# ProPrj_32__2025-06-29.net
KiCad netlist of a schematic drawn in EasyEDA Pro
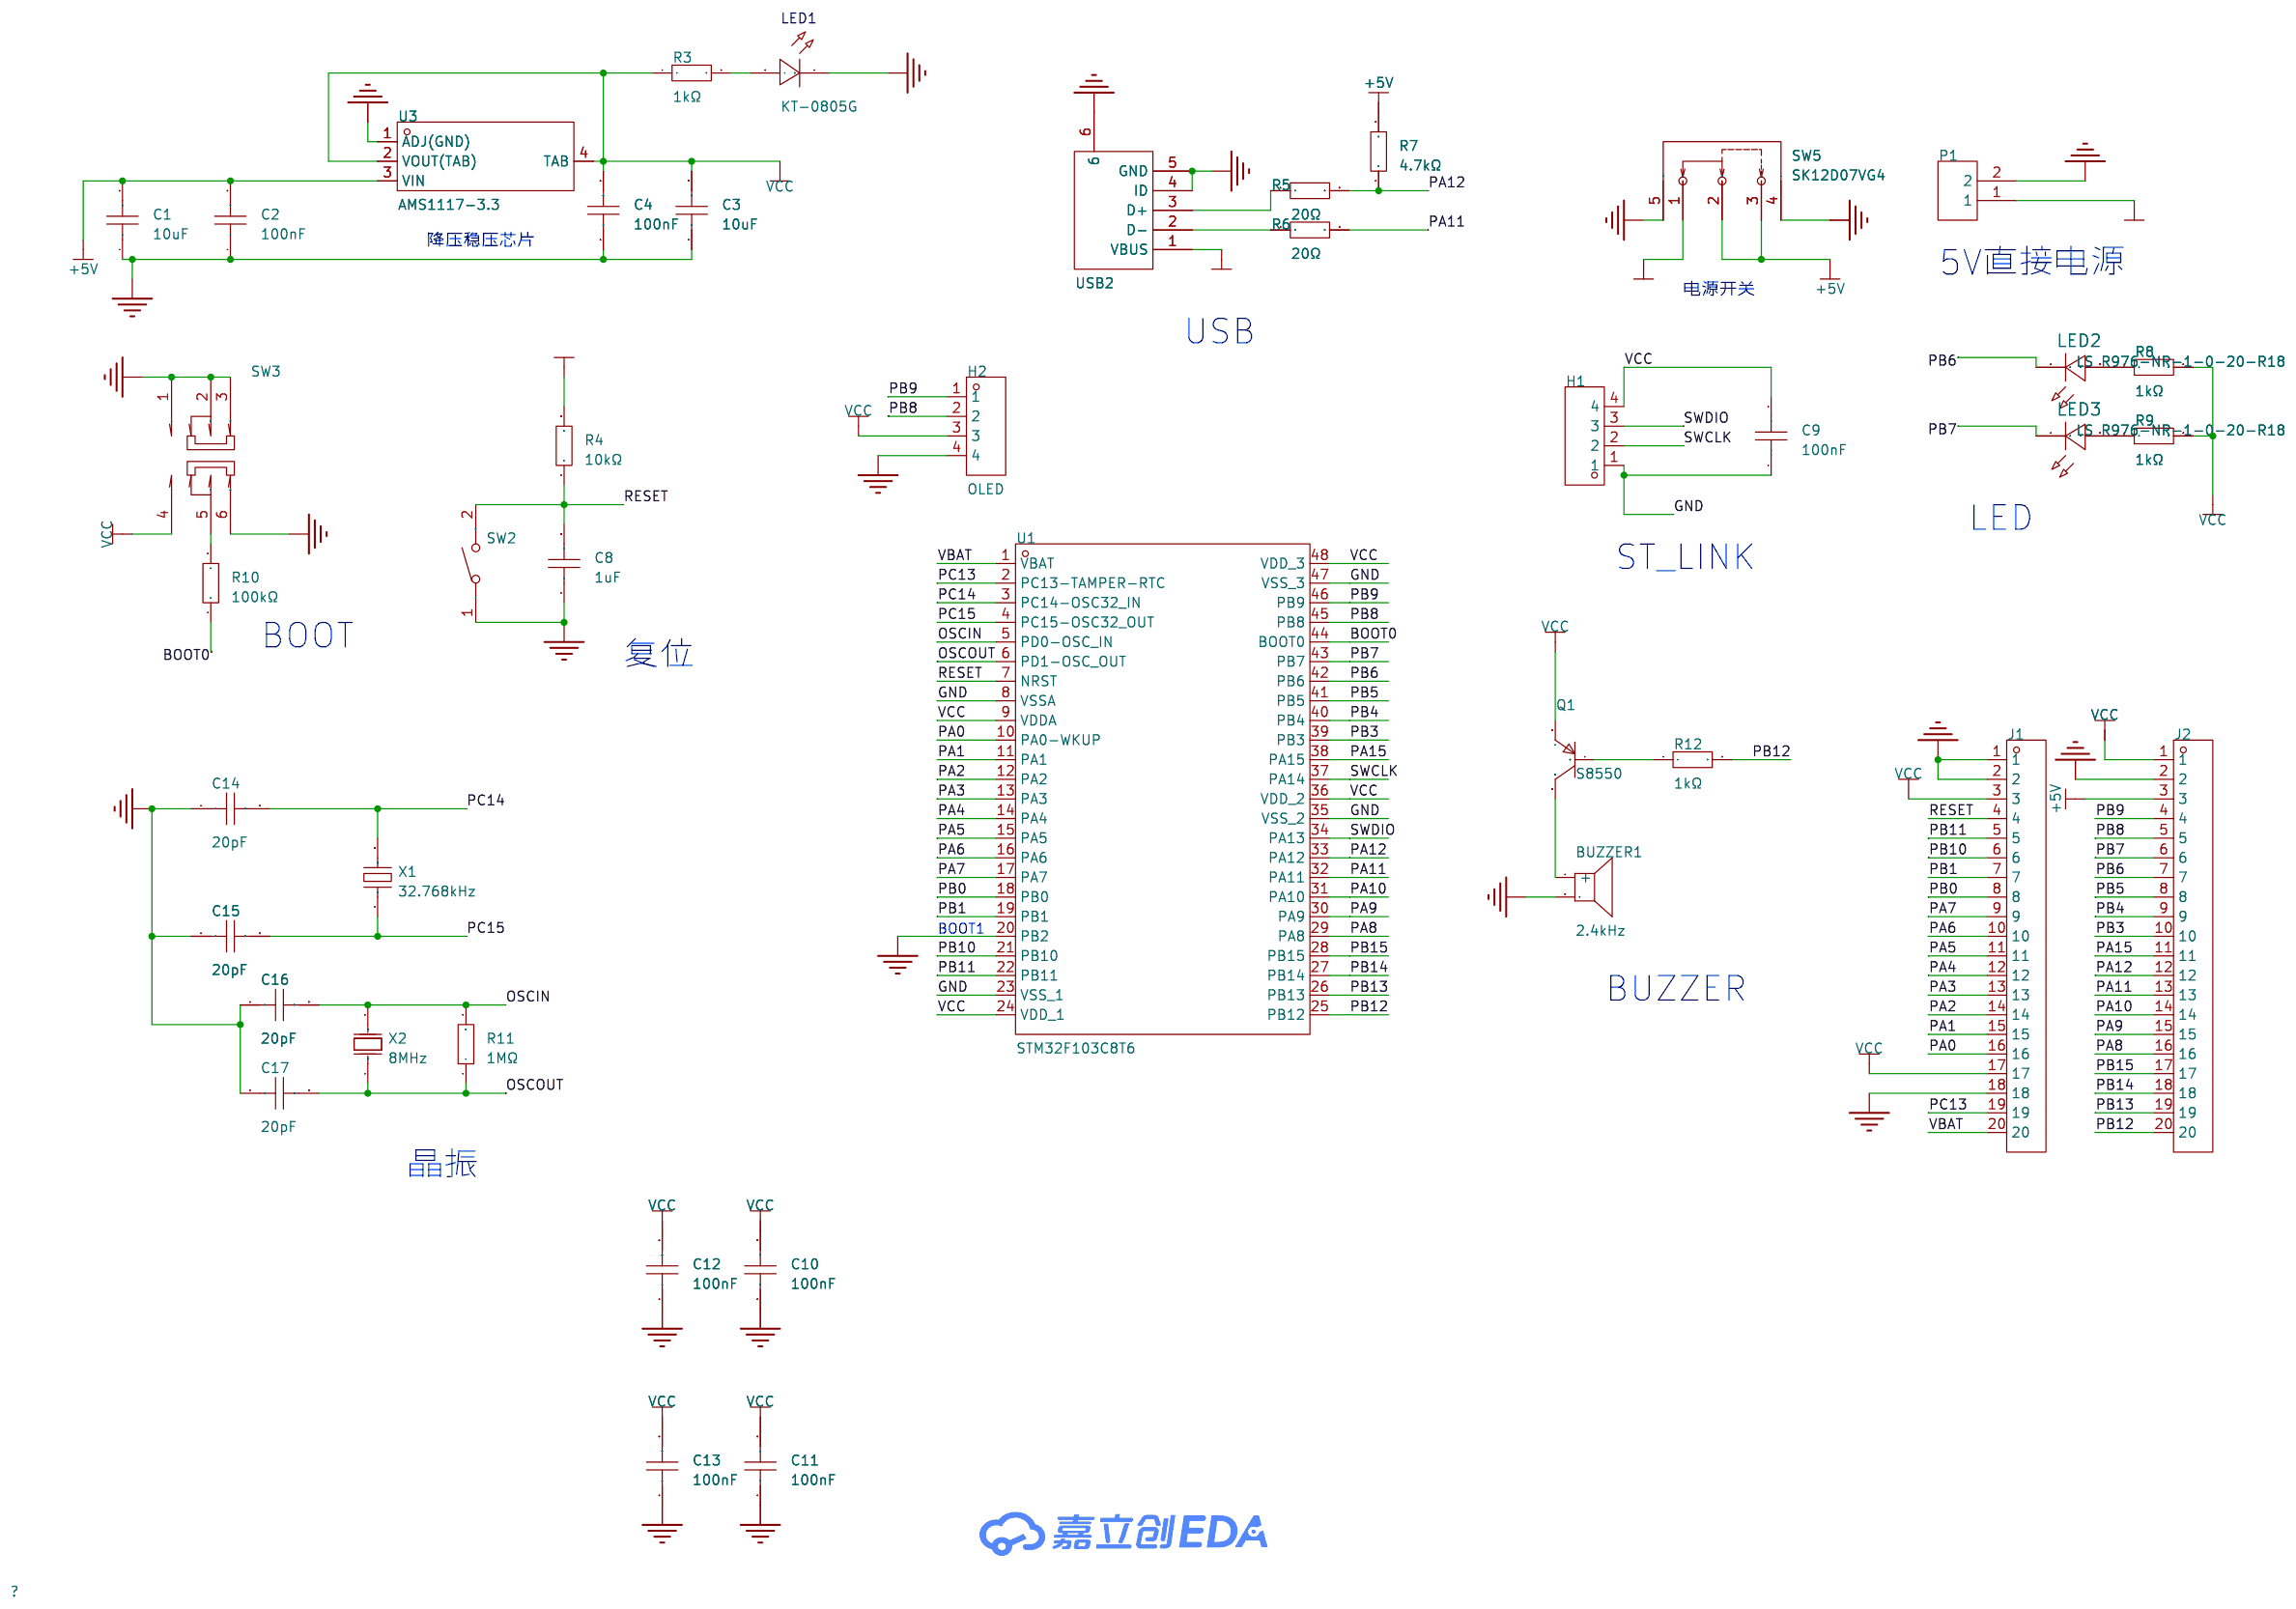
[diagram p0: P1]
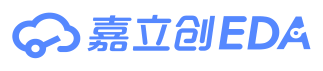
[diagram p1: P2]

(export (version "E")
  (design (tool "Eeschema 10.0.6"))
  (components
    (comp (ref "BUZZER1")
      (value "2.4kHz")
      (footprint "easyedapro:BUZ-TH_BD12.0-P7.60-D0.6-FD")
      (description "驱动方式:有源(内含驱动线路);构造类型:电磁式;额定电压:-;频率:2.4kHz;声压(SPL):85dB;")
      (fields (field (name "Manufacturer Part") "TMB12A05") (field (name "Manufacturer") "华能"))
      (libsource (lib "easyedapro") (part "TMB12A05"))
    )
    (comp (ref "C1")
      (value "10uF")
      (footprint "easyedapro:C0805")
      (fields
        (field (name "Manufacturer Part") "CL21A106KOQNNNE")
        (field (name "Manufacturer") "SAMSUNG(三星)")
      )
      (libsource (lib "easyedapro") (part "CapAcitance"))
    )
    (comp (ref "C2")
      (value "100nF")
      (footprint "easyedapro:C0805")
      (fields
        (field (name "Manufacturer Part") "CC0805KRX7R9BB104")
        (field (name "Manufacturer") "YAGEO(国巨)")
      )
      (libsource (lib "easyedapro") (part "CapAcitance"))
    )
    (comp (ref "C3")
      (value "10uF")
      (footprint "easyedapro:C0805")
      (fields
        (field (name "Manufacturer Part") "CL21A106KOQNNNE")
        (field (name "Manufacturer") "SAMSUNG(三星)")
      )
      (libsource (lib "easyedapro") (part "CapAcitance"))
    )
    (comp (ref "C4")
      (value "100nF")
      (footprint "easyedapro:C0805")
      (fields
        (field (name "Manufacturer Part") "CC0805KRX7R9BB104")
        (field (name "Manufacturer") "YAGEO(国巨)")
      )
      (libsource (lib "easyedapro") (part "CapAcitance"))
    )
    (comp (ref "C8")
      (value "1uF")
      (footprint "easyedapro:C0805")
      (fields
        (field (name "Manufacturer Part") "CL21B105KBFNNNE")
        (field (name "Manufacturer") "SAMSUNG(三星)")
      )
      (libsource (lib "easyedapro") (part "CapAcitance"))
    )
    (comp (ref "C9")
      (value "100nF")
      (footprint "easyedapro:C0805")
      (fields
        (field (name "Manufacturer Part") "CC0805KRX7R9BB104")
        (field (name "Manufacturer") "YAGEO(国巨)")
      )
      (libsource (lib "easyedapro") (part "CapAcitance"))
    )
    (comp (ref "C10")
      (value "100nF")
      (footprint "easyedapro:C0805")
      (fields
        (field (name "Manufacturer Part") "CC0805KRX7R9BB104")
        (field (name "Manufacturer") "YAGEO(国巨)")
      )
      (libsource (lib "easyedapro") (part "CapAcitance"))
    )
    (comp (ref "C11")
      (value "100nF")
      (footprint "easyedapro:C0805")
      (fields
        (field (name "Manufacturer Part") "CC0805KRX7R9BB104")
        (field (name "Manufacturer") "YAGEO(国巨)")
      )
      (libsource (lib "easyedapro") (part "CapAcitance"))
    )
    (comp (ref "C12")
      (value "100nF")
      (footprint "easyedapro:C0805")
      (fields
        (field (name "Manufacturer Part") "CC0805KRX7R9BB104")
        (field (name "Manufacturer") "YAGEO(国巨)")
      )
      (libsource (lib "easyedapro") (part "CapAcitance"))
    )
    (comp (ref "C13")
      (value "100nF")
      (footprint "easyedapro:C0805")
      (fields
        (field (name "Manufacturer Part") "CC0805KRX7R9BB104")
        (field (name "Manufacturer") "YAGEO(国巨)")
      )
      (libsource (lib "easyedapro") (part "CapAcitance"))
    )
    (comp (ref "C14")
      (value "20pF")
      (footprint "easyedapro:C0805")
      (fields
        (field (name "Manufacturer Part") "CL21C200JBANNNC")
        (field (name "Manufacturer") "SAMSUNG(三星)")
      )
      (libsource (lib "easyedapro") (part "CapAcitance"))
    )
    (comp (ref "C15")
      (value "20pF")
      (footprint "easyedapro:C0805")
      (fields
        (field (name "Manufacturer Part") "CL21C200JBANNNC")
        (field (name "Manufacturer") "SAMSUNG(三星)")
      )
      (libsource (lib "easyedapro") (part "CapAcitance"))
    )
    (comp (ref "C16")
      (value "20pF")
      (footprint "easyedapro:C0805")
      (fields
        (field (name "Manufacturer Part") "CL21C200JBANNNC")
        (field (name "Manufacturer") "SAMSUNG(三星)")
      )
      (libsource (lib "easyedapro") (part "CapAcitance"))
    )
    (comp (ref "C17")
      (value "20pF")
      (footprint "easyedapro:C0805")
      (fields
        (field (name "Manufacturer Part") "CL21C200JBANNNC")
        (field (name "Manufacturer") "SAMSUNG(三星)")
      )
      (libsource (lib "easyedapro") (part "CapAcitance"))
    )
    (comp (ref "H1")
      (value "PZ254V-11-04P")
      (footprint "easyedapro:HDR-TH_4P-P2.54-V-M")
      (fields (field (name "Manufacturer") "XFCN(兴飞)"))
      (libsource (lib "easyedapro") (part "PZ254V-11-04P_C2691448"))
    )
    (comp (ref "H2")
      (value "OLED")
      (footprint "easyedapro:HDR-TH_4P-P2.54-V-F")
      (fields (field (name "Manufacturer") "BOOMELE(博穆精密)"))
      (libsource (lib "easyedapro") (part "2.54-1*4P母"))
    )
    (comp (ref "J1")
      (value "2.54-1*20P直针")
      (footprint "easyedapro:HDR-TH_20P-P2.54-V-M-1")
      (fields (field (name "Manufacturer") "BOOMELE(博穆精密)"))
      (libsource (lib "easyedapro") (part "Header-Male-2.54_1x20"))
    )
    (comp (ref "J2")
      (value "2.54-1*20P直针")
      (footprint "easyedapro:HDR-TH_20P-P2.54-V-M-1")
      (fields (field (name "Manufacturer") "BOOMELE(博穆精密)"))
      (libsource (lib "easyedapro") (part "Header-Male-2.54_1x20"))
    )
    (comp (ref "LED1")
      (value "KT-0805G")
      (fields (field (name "Manufacturer") "KENTO"))
      (libsource (lib "easyedapro") (part "LED_G"))
    )
    (comp (ref "LED2")
      (value "LS R976-NR-1-0-20-R18")
      (fields (field (name "Manufacturer") "OSRAM(欧司朗)"))
      (libsource (lib "easyedapro") (part "LED_R"))
    )
    (comp (ref "LED3")
      (value "LS R976-NR-1-0-20-R18")
      (fields (field (name "Manufacturer") "OSRAM(欧司朗)"))
      (libsource (lib "easyedapro") (part "LED_R"))
    )
    (comp (ref "P1")
      (value "WJ500V-5.08-2P")
      (footprint "easyedapro:CONN-TH_2P-P5.00_WJ500V-5.08-2P")
      (fields (field (name "Manufacturer") "KANGNEX(康奈克斯电气)"))
      (libsource (lib "easyedapro") (part "WJ500V-5.08-2P-14-00A"))
    )
    (comp (ref "Q1")
      (value "S8550")
      (footprint "easyedapro:SOT-23-3_L2.9-W1.3-P1.90-LS2.4-BR")
      (description "晶体管类型:PNP;集电极电流(Ic):500mA;集射极击穿电压(Vceo):25V;功率(Pd):300mW;直流电流增益(hFE@Ic,Vce):120@50mA,1V;")
      (fields (field (name "Manufacturer") "HXY MOSFET(华轩阳电子)"))
      (libsource (lib "easyedapro") (part "S8550_C5184407"))
    )
    (comp (ref "R3")
      (value "1kΩ")
      (footprint "easyedapro:R0805")
      (fields
        (field (name "Manufacturer Part") "0805W8F1001T5E")
        (field (name "Manufacturer") "UNI-ROYAL(厚声)")
      )
      (libsource (lib "easyedapro") (part "电阻"))
    )
    (comp (ref "R4")
      (value "10kΩ")
      (footprint "easyedapro:R0805")
      (fields
        (field (name "Manufacturer Part") "0805W8F1002T5E")
        (field (name "Manufacturer") "UNI-ROYAL(厚声)")
      )
      (libsource (lib "easyedapro") (part "电阻"))
    )
    (comp (ref "R5")
      (value "20Ω")
      (footprint "easyedapro:R0805")
      (fields
        (field (name "Manufacturer Part") "0805W8F200JT5E")
        (field (name "Manufacturer") "UNI-ROYAL(厚声)")
      )
      (libsource (lib "easyedapro") (part "电阻"))
    )
    (comp (ref "R6")
      (value "20Ω")
      (footprint "easyedapro:R0805")
      (fields
        (field (name "Manufacturer Part") "0805W8F200JT5E")
        (field (name "Manufacturer") "UNI-ROYAL(厚声)")
      )
      (libsource (lib "easyedapro") (part "电阻"))
    )
    (comp (ref "R7")
      (value "4.7kΩ")
      (footprint "easyedapro:R0805")
      (fields
        (field (name "Manufacturer Part") "0805W8F4701T5E")
        (field (name "Manufacturer") "UNI-ROYAL(厚声)")
      )
      (libsource (lib "easyedapro") (part "电阻"))
    )
    (comp (ref "R8")
      (value "1kΩ")
      (footprint "easyedapro:R0805")
      (fields
        (field (name "Manufacturer Part") "0805W8F1001T5E")
        (field (name "Manufacturer") "UNI-ROYAL(厚声)")
      )
      (libsource (lib "easyedapro") (part "电阻"))
    )
    (comp (ref "R9")
      (value "1kΩ")
      (footprint "easyedapro:R0805")
      (fields
        (field (name "Manufacturer Part") "0805W8F1001T5E")
        (field (name "Manufacturer") "UNI-ROYAL(厚声)")
      )
      (libsource (lib "easyedapro") (part "电阻"))
    )
    (comp (ref "R10")
      (value "100kΩ")
      (footprint "easyedapro:R0805")
      (fields
        (field (name "Manufacturer Part") "0805W8F1003T5E")
        (field (name "Manufacturer") "UNI-ROYAL(厚声)")
      )
      (libsource (lib "easyedapro") (part "电阻"))
    )
    (comp (ref "R11")
      (value "1MΩ")
      (footprint "easyedapro:R0805")
      (fields
        (field (name "Manufacturer Part") "0805W8F1004T5E")
        (field (name "Manufacturer") "UNI-ROYAL(厚声)")
      )
      (libsource (lib "easyedapro") (part "电阻"))
    )
    (comp (ref "R12")
      (value "1kΩ")
      (footprint "easyedapro:R0805")
      (fields
        (field (name "Manufacturer Part") "0805W8F1001T5E")
        (field (name "Manufacturer") "UNI-ROYAL(厚声)")
      )
      (libsource (lib "easyedapro") (part "电阻"))
    )
    (comp (ref "SW2")
      (value "TS-1088-AR02016")
      (footprint "easyedapro:SW-SMD_L3.9-W3.0-P4.45")
      (fields (field (name "Manufacturer") "XUNPU(讯普)"))
      (libsource (lib "easyedapro") (part "TS-1088-AR02016"))
    )
    (comp (ref "SW3")
      (value "SS-3235S-L1")
      (footprint "easyedapro:SW-SMD_SS-3235S-LX")
      (description "电路结构:双刀双掷;安装方式:卧贴;开关颜色:黑色;额定电流(DC):50mA;额定电压(DC):12V;额定电流(AC):50mA;额定电压(AC):12V;机械寿命:1万次;")
      (fields (field (name "Manufacturer") "XKB Connectivity(中国星坤)"))
      (libsource (lib "easyedapro") (part "SS-3235S-L1"))
    )
    (comp (ref "SW5")
      (value "SK12D07VG4")
      (footprint "easyedapro:SW-TH_SK12D07VG4")
      (description "电路结构:单刀双掷;安装方式:-;额定电流(DC):500mA;额定电压(DC):50V;额定电流(AC):-;额定电压(AC):-;机械寿命:5千次;")
      (fields (field (name "Manufacturer") "SHOU HAN(首韩)"))
      (libsource (lib "easyedapro") (part "SK12D07VG4"))
    )
    (comp (ref "U1")
      (value "STM32F103C8T6")
      (footprint "easyedapro:LQFP-48_L7.0-W7.0-P0.50-LS9.0-BL")
      (description "CPU内核:ARM-M3;CPU最大主频:72MHz;应用领域:-;")
      (fields (field (name "Manufacturer") "ST(意法半导体)"))
      (libsource (lib "easyedapro") (part "STM32F103C8T6"))
    )
    (comp (ref "U3")
      (value "AMS1117-3.3")
      (footprint "easyedapro:SOT-223-4_L6.5-W3.5-P2.30-LS7.0-BR")
      (description "输出类型:固定;工作电压:12V;输出电压:3.3V;输出电流:1A;电源纹波抑制比(PSRR):60dB@(120Hz);输出极性:正极;")
      (fields (field (name "Manufacturer") "UMW(友台半导体)"))
      (libsource (lib "easyedapro") (part "AMS1117-3.3_C347222"))
    )
    (comp (ref "USB2")
      (value "MICRO5.9mmusb")
      (footprint "easyedapro:MICRO-USB-SMD_5P-P0.65-H-F_MICRO5.9MMUSB")
      (description "连接器类型:Micro-B;标准:USB 2.0;公母:母;安装方式:卧贴;触点数量:5P;端口数量:1;额定电流 - 电源:1A;工作温度范围:-30°C~+80°C;")
      (fields (field (name "Manufacturer") "SHOU HAN(首韩)"))
      (libsource (lib "easyedapro") (part "MICRO5.9MMUSB"))
    )
    (comp (ref "X1")
      (value "32.768kHz")
      (footprint "easyedapro:CRYSTAL-SMD_L7.0-W3.2-LS7.5")
      (description "晶振类型:贴片晶振;频率:32.768kHz;常温频差:±20ppm;外接负载电容:12.5pF;频率稳定度(全温):±20ppm;")
      (fields
        (field (name "Manufacturer Part") "FL37S2-32.768-NLLLDTL")
        (field (name "Manufacturer") "HCI(杭晶)")
      )
      (libsource (lib "easyedapro") (part "FL37S2-32.768-NLLLDTL"))
    )
    (comp (ref "X2")
      (value "8MHz")
      (footprint "easyedapro:HC-49US_L11.5-W4.5-P4.88")
      (description "晶振类型:直插晶振;频率:8MHz;常温频差:±30ppm;外接负载电容:20pF;频率稳定度(全温):±30ppm;")
      (fields (field (name "Manufacturer Part") "TAXD8M2GLFBET2T") (field (name "Manufacturer") "YJX(雅晶鑫)"))
      (libsource (lib "easyedapro") (part "HC-49S 8MHz 20pF 30PPM"))
    )
  )
  (nets
    (net (code "1") (name "+5V") (class "Default")
      (node (ref "C1") (pin "2") (pinfunction "2_2") (pintype "input"))
      (node (ref "C2") (pin "2") (pinfunction "2_2") (pintype "input"))
      (node (ref "J2") (pin "3") (pinfunction "3_3") (pintype "unspecified"))
      (node (ref "R7") (pin "2") (pinfunction "2_2") (pintype "input"))
      (node (ref "SW5") (pin "2") (pinfunction "2_2") (pintype "unspecified"))
      (node (ref "SW5") (pin "3") (pinfunction "3_3") (pintype "unspecified"))
      (node (ref "U3") (pin "3") (pinfunction "VIN_3") (pintype "unspecified"))
    )
    (net (code "2") (name "+5V_IN") (class "Default")
      (node (ref "P1") (pin "1") (pinfunction "1_1") (pintype "unspecified"))
      (node (ref "SW5") (pin "1") (pinfunction "1_1") (pintype "unspecified"))
      (node (ref "USB2") (pin "1") (pinfunction "VBUS_1") (pintype "unspecified"))
    )
    (net (code "3") (name "BOOT0") (class "Default")
      (node (ref "R10") (pin "1") (pinfunction "1_1") (pintype "input"))
      (node (ref "U1") (pin "44") (pinfunction "BOOT0_44") (pintype "unspecified"))
    )
    (net (code "4") (name "GND") (class "Default")
      (node (ref "BUZZER1") (pin "2") (pinfunction "2_2") (pintype "unspecified"))
      (node (ref "C1") (pin "1") (pinfunction "1_1") (pintype "input"))
      (node (ref "C10") (pin "1") (pinfunction "1_1") (pintype "input"))
      (node (ref "C11") (pin "1") (pinfunction "1_1") (pintype "input"))
      (node (ref "C12") (pin "1") (pinfunction "1_1") (pintype "input"))
      (node (ref "C13") (pin "1") (pinfunction "1_1") (pintype "input"))
      (node (ref "C14") (pin "1") (pinfunction "1_1") (pintype "input"))
      (node (ref "C15") (pin "1") (pinfunction "1_1") (pintype "input"))
      (node (ref "C16") (pin "1") (pinfunction "1_1") (pintype "input"))
      (node (ref "C17") (pin "1") (pinfunction "1_1") (pintype "input"))
      (node (ref "C2") (pin "1") (pinfunction "1_1") (pintype "input"))
      (node (ref "C3") (pin "1") (pinfunction "1_1") (pintype "input"))
      (node (ref "C4") (pin "1") (pinfunction "1_1") (pintype "input"))
      (node (ref "C8") (pin "1") (pinfunction "1_1") (pintype "input"))
      (node (ref "C9") (pin "1") (pinfunction "1_1") (pintype "input"))
      (node (ref "H1") (pin "1") (pinfunction "1_1") (pintype "unspecified"))
      (node (ref "H2") (pin "4") (pinfunction "4_4") (pintype "unspecified"))
      (node (ref "J1") (pin "1") (pinfunction "1_1") (pintype "unspecified"))
      (node (ref "J1") (pin "18") (pinfunction "18_18") (pintype "unspecified"))
      (node (ref "J1") (pin "2") (pinfunction "2_2") (pintype "unspecified"))
      (node (ref "J2") (pin "2") (pinfunction "2_2") (pintype "unspecified"))
      (node (ref "LED1") (pin "1") (pinfunction "C_1") (pintype "input"))
      (node (ref "P1") (pin "2") (pinfunction "2_2") (pintype "unspecified"))
      (node (ref "SW2") (pin "1") (pinfunction "1_1") (pintype "unspecified"))
      (node (ref "SW3") (pin "1") (pinfunction "1_1") (pintype "unspecified"))
      (node (ref "SW3") (pin "2") (pinfunction "2_2") (pintype "unspecified"))
      (node (ref "SW3") (pin "3") (pinfunction "3_3") (pintype "unspecified"))
      (node (ref "SW3") (pin "6") (pinfunction "6_6") (pintype "unspecified"))
      (node (ref "SW5") (pin "4") (pinfunction "4_4") (pintype "unspecified"))
      (node (ref "SW5") (pin "5") (pinfunction "5_5") (pintype "unspecified"))
      (node (ref "U1") (pin "20") (pinfunction "PB2_20") (pintype "unspecified"))
      (node (ref "U1") (pin "23") (pinfunction "VSS_1_23") (pintype "unspecified"))
      (node (ref "U1") (pin "35") (pinfunction "VSS_2_35") (pintype "unspecified"))
      (node (ref "U1") (pin "47") (pinfunction "VSS_3_47") (pintype "unspecified"))
      (node (ref "U1") (pin "8") (pinfunction "VSSA_8") (pintype "unspecified"))
      (node (ref "U3") (pin "1") (pinfunction "ADJ(GND)_1") (pintype "unspecified"))
      (node (ref "USB2") (pin "4") (pinfunction "ID_4") (pintype "unspecified"))
      (node (ref "USB2") (pin "5") (pinfunction "GND_5") (pintype "unspecified"))
      (node (ref "USB2") (pin "6") (pinfunction "6_6") (pintype "unspecified"))
    )
    (net (code "5") (name "Net-(BUZZER1-+)") (class "Default")
      (node (ref "BUZZER1") (pin "1") (pinfunction "+_1") (pintype "unspecified"))
      (node (ref "Q1") (pin "3") (pinfunction "C_3") (pintype "input"))
    )
    (net (code "6") (name "Net-(LED1-A)") (class "Default")
      (node (ref "LED1") (pin "2") (pinfunction "A_2") (pintype "input"))
      (node (ref "R3") (pin "2") (pinfunction "2_2") (pintype "input"))
    )
    (net (code "7") (name "Net-(LED2-A)") (class "Default")
      (node (ref "LED2") (pin "2") (pinfunction "A_2") (pintype "input"))
      (node (ref "R8") (pin "1") (pinfunction "1_1") (pintype "input"))
    )
    (net (code "8") (name "Net-(LED3-A)") (class "Default")
      (node (ref "LED3") (pin "2") (pinfunction "A_2") (pintype "input"))
      (node (ref "R9") (pin "1") (pinfunction "1_1") (pintype "input"))
    )
    (net (code "9") (name "Net-(Q1-B)") (class "Default")
      (node (ref "Q1") (pin "1") (pinfunction "B_1") (pintype "input"))
      (node (ref "R12") (pin "1") (pinfunction "1_1") (pintype "input"))
    )
    (net (code "10") (name "Net-(R10-Pad2)") (class "Default")
      (node (ref "R10") (pin "2") (pinfunction "2_2") (pintype "input"))
      (node (ref "SW3") (pin "5") (pinfunction "5_5") (pintype "unspecified"))
    )
    (net (code "11") (name "Net-(USB2-D+)") (class "Default")
      (node (ref "R5") (pin "1") (pinfunction "1_1") (pintype "input"))
      (node (ref "USB2") (pin "3") (pinfunction "D+_3") (pintype "unspecified"))
    )
    (net (code "12") (name "Net-(USB2-D-)") (class "Default")
      (node (ref "R6") (pin "1") (pinfunction "1_1") (pintype "input"))
      (node (ref "USB2") (pin "2") (pinfunction "D-_2") (pintype "unspecified"))
    )
    (net (code "13") (name "OSCIN") (class "Default")
      (node (ref "C16") (pin "2") (pinfunction "2_2") (pintype "input"))
      (node (ref "R11") (pin "2") (pinfunction "2_2") (pintype "input"))
      (node (ref "U1") (pin "5") (pinfunction "PD0-OSC_IN_5") (pintype "unspecified"))
      (node (ref "X2") (pin "2") (pinfunction "OSC2_2") (pintype "input"))
    )
    (net (code "14") (name "OSCOUT") (class "Default")
      (node (ref "C17") (pin "2") (pinfunction "2_2") (pintype "input"))
      (node (ref "R11") (pin "1") (pinfunction "1_1") (pintype "input"))
      (node (ref "U1") (pin "6") (pinfunction "PD1-OSC_OUT_6") (pintype "unspecified"))
      (node (ref "X2") (pin "1") (pinfunction "OSC1_1") (pintype "input"))
    )
    (net (code "15") (name "PA0") (class "Default")
      (node (ref "J1") (pin "16") (pinfunction "16_16") (pintype "unspecified"))
      (node (ref "U1") (pin "10") (pinfunction "PA0-WKUP_10") (pintype "unspecified"))
    )
    (net (code "16") (name "PA1") (class "Default")
      (node (ref "J1") (pin "15") (pinfunction "15_15") (pintype "unspecified"))
      (node (ref "U1") (pin "11") (pinfunction "PA1_11") (pintype "unspecified"))
    )
    (net (code "17") (name "PA2") (class "Default")
      (node (ref "J1") (pin "14") (pinfunction "14_14") (pintype "unspecified"))
      (node (ref "U1") (pin "12") (pinfunction "PA2_12") (pintype "unspecified"))
    )
    (net (code "18") (name "PA3") (class "Default")
      (node (ref "J1") (pin "13") (pinfunction "13_13") (pintype "unspecified"))
      (node (ref "U1") (pin "13") (pinfunction "PA3_13") (pintype "unspecified"))
    )
    (net (code "19") (name "PA4") (class "Default")
      (node (ref "J1") (pin "12") (pinfunction "12_12") (pintype "unspecified"))
      (node (ref "U1") (pin "14") (pinfunction "PA4_14") (pintype "unspecified"))
    )
    (net (code "20") (name "PA5") (class "Default")
      (node (ref "J1") (pin "11") (pinfunction "11_11") (pintype "unspecified"))
      (node (ref "U1") (pin "15") (pinfunction "PA5_15") (pintype "unspecified"))
    )
    (net (code "21") (name "PA6") (class "Default")
      (node (ref "J1") (pin "10") (pinfunction "10_10") (pintype "unspecified"))
      (node (ref "U1") (pin "16") (pinfunction "PA6_16") (pintype "unspecified"))
    )
    (net (code "22") (name "PA7") (class "Default")
      (node (ref "J1") (pin "9") (pinfunction "9_9") (pintype "unspecified"))
      (node (ref "U1") (pin "17") (pinfunction "PA7_17") (pintype "unspecified"))
    )
    (net (code "23") (name "PA8") (class "Default")
      (node (ref "J2") (pin "16") (pinfunction "16_16") (pintype "unspecified"))
      (node (ref "U1") (pin "29") (pinfunction "PA8_29") (pintype "unspecified"))
    )
    (net (code "24") (name "PA9") (class "Default")
      (node (ref "J2") (pin "15") (pinfunction "15_15") (pintype "unspecified"))
      (node (ref "U1") (pin "30") (pinfunction "PA9_30") (pintype "unspecified"))
    )
    (net (code "25") (name "PA10") (class "Default")
      (node (ref "J2") (pin "14") (pinfunction "14_14") (pintype "unspecified"))
      (node (ref "U1") (pin "31") (pinfunction "PA10_31") (pintype "unspecified"))
    )
    (net (code "26") (name "PA11") (class "Default")
      (node (ref "J2") (pin "13") (pinfunction "13_13") (pintype "unspecified"))
      (node (ref "R6") (pin "2") (pinfunction "2_2") (pintype "input"))
      (node (ref "U1") (pin "32") (pinfunction "PA11_32") (pintype "unspecified"))
    )
    (net (code "27") (name "PA12") (class "Default")
      (node (ref "J2") (pin "12") (pinfunction "12_12") (pintype "unspecified"))
      (node (ref "R5") (pin "2") (pinfunction "2_2") (pintype "input"))
      (node (ref "R7") (pin "1") (pinfunction "1_1") (pintype "input"))
      (node (ref "U1") (pin "33") (pinfunction "PA12_33") (pintype "unspecified"))
    )
    (net (code "28") (name "PA15") (class "Default")
      (node (ref "J2") (pin "11") (pinfunction "11_11") (pintype "unspecified"))
      (node (ref "U1") (pin "38") (pinfunction "PA15_38") (pintype "unspecified"))
    )
    (net (code "29") (name "PB0") (class "Default")
      (node (ref "J1") (pin "8") (pinfunction "8_8") (pintype "unspecified"))
      (node (ref "U1") (pin "18") (pinfunction "PB0_18") (pintype "unspecified"))
    )
    (net (code "30") (name "PB1") (class "Default")
      (node (ref "J1") (pin "7") (pinfunction "7_7") (pintype "unspecified"))
      (node (ref "U1") (pin "19") (pinfunction "PB1_19") (pintype "unspecified"))
    )
    (net (code "31") (name "PB3") (class "Default")
      (node (ref "J2") (pin "10") (pinfunction "10_10") (pintype "unspecified"))
      (node (ref "U1") (pin "39") (pinfunction "PB3_39") (pintype "unspecified"))
    )
    (net (code "32") (name "PB4") (class "Default")
      (node (ref "J2") (pin "9") (pinfunction "9_9") (pintype "unspecified"))
      (node (ref "U1") (pin "40") (pinfunction "PB4_40") (pintype "unspecified"))
    )
    (net (code "33") (name "PB5") (class "Default")
      (node (ref "J2") (pin "8") (pinfunction "8_8") (pintype "unspecified"))
      (node (ref "U1") (pin "41") (pinfunction "PB5_41") (pintype "unspecified"))
    )
    (net (code "34") (name "PB6") (class "Default")
      (node (ref "J2") (pin "7") (pinfunction "7_7") (pintype "unspecified"))
      (node (ref "LED2") (pin "1") (pinfunction "C_1") (pintype "input"))
      (node (ref "U1") (pin "42") (pinfunction "PB6_42") (pintype "unspecified"))
    )
    (net (code "35") (name "PB7") (class "Default")
      (node (ref "J2") (pin "6") (pinfunction "6_6") (pintype "unspecified"))
      (node (ref "LED3") (pin "1") (pinfunction "C_1") (pintype "input"))
      (node (ref "U1") (pin "43") (pinfunction "PB7_43") (pintype "unspecified"))
    )
    (net (code "36") (name "PB8") (class "Default")
      (node (ref "H2") (pin "2") (pinfunction "2_2") (pintype "unspecified"))
      (node (ref "J2") (pin "5") (pinfunction "5_5") (pintype "unspecified"))
      (node (ref "U1") (pin "45") (pinfunction "PB8_45") (pintype "unspecified"))
    )
    (net (code "37") (name "PB9") (class "Default")
      (node (ref "H2") (pin "1") (pinfunction "1_1") (pintype "unspecified"))
      (node (ref "J2") (pin "4") (pinfunction "4_4") (pintype "unspecified"))
      (node (ref "U1") (pin "46") (pinfunction "PB9_46") (pintype "unspecified"))
    )
    (net (code "38") (name "PB10") (class "Default")
      (node (ref "J1") (pin "6") (pinfunction "6_6") (pintype "unspecified"))
      (node (ref "U1") (pin "21") (pinfunction "PB10_21") (pintype "unspecified"))
    )
    (net (code "39") (name "PB11") (class "Default")
      (node (ref "J1") (pin "5") (pinfunction "5_5") (pintype "unspecified"))
      (node (ref "U1") (pin "22") (pinfunction "PB11_22") (pintype "unspecified"))
    )
    (net (code "40") (name "PB12") (class "Default")
      (node (ref "J2") (pin "20") (pinfunction "20_20") (pintype "unspecified"))
      (node (ref "R12") (pin "2") (pinfunction "2_2") (pintype "input"))
      (node (ref "U1") (pin "25") (pinfunction "PB12_25") (pintype "unspecified"))
    )
    (net (code "41") (name "PB13") (class "Default")
      (node (ref "J2") (pin "19") (pinfunction "19_19") (pintype "unspecified"))
      (node (ref "U1") (pin "26") (pinfunction "PB13_26") (pintype "unspecified"))
    )
    (net (code "42") (name "PB14") (class "Default")
      (node (ref "J2") (pin "18") (pinfunction "18_18") (pintype "unspecified"))
      (node (ref "U1") (pin "27") (pinfunction "PB14_27") (pintype "unspecified"))
    )
    (net (code "43") (name "PB15") (class "Default")
      (node (ref "J2") (pin "17") (pinfunction "17_17") (pintype "unspecified"))
      (node (ref "U1") (pin "28") (pinfunction "PB15_28") (pintype "unspecified"))
    )
    (net (code "44") (name "PC13") (class "Default")
      (node (ref "J1") (pin "19") (pinfunction "19_19") (pintype "unspecified"))
      (node (ref "U1") (pin "2") (pinfunction "PC13-TAMPER-RTC_2") (pintype "unspecified"))
    )
    (net (code "45") (name "PC14") (class "Default")
      (node (ref "C14") (pin "2") (pinfunction "2_2") (pintype "input"))
      (node (ref "U1") (pin "3") (pinfunction "PC14-OSC32_IN_3") (pintype "unspecified"))
      (node (ref "X1") (pin "2") (pinfunction "GND_2") (pintype "input"))
    )
    (net (code "46") (name "PC15") (class "Default")
      (node (ref "C15") (pin "2") (pinfunction "2_2") (pintype "input"))
      (node (ref "U1") (pin "4") (pinfunction "PC15-OSC32_OUT_4") (pintype "unspecified"))
      (node (ref "X1") (pin "1") (pinfunction "1_1") (pintype "input"))
    )
    (net (code "47") (name "RESET") (class "Default")
      (node (ref "C8") (pin "2") (pinfunction "2_2") (pintype "input"))
      (node (ref "J1") (pin "4") (pinfunction "4_4") (pintype "unspecified"))
      (node (ref "R4") (pin "1") (pinfunction "1_1") (pintype "input"))
      (node (ref "SW2") (pin "2") (pinfunction "2_2") (pintype "unspecified"))
      (node (ref "U1") (pin "7") (pinfunction "NRST_7") (pintype "unspecified"))
    )
    (net (code "48") (name "SWCLK") (class "Default")
      (node (ref "H1") (pin "2") (pinfunction "2_2") (pintype "unspecified"))
      (node (ref "U1") (pin "37") (pinfunction "PA14_37") (pintype "unspecified"))
    )
    (net (code "49") (name "SWDIO") (class "Default")
      (node (ref "H1") (pin "3") (pinfunction "3_3") (pintype "unspecified"))
      (node (ref "U1") (pin "34") (pinfunction "PA13_34") (pintype "unspecified"))
    )
    (net (code "50") (name "VBAT") (class "Default")
      (node (ref "J1") (pin "20") (pinfunction "20_20") (pintype "unspecified"))
      (node (ref "U1") (pin "1") (pinfunction "VBAT_1") (pintype "unspecified"))
    )
    (net (code "51") (name "VCC") (class "Default")
      (node (ref "C10") (pin "2") (pinfunction "2_2") (pintype "input"))
      (node (ref "C11") (pin "2") (pinfunction "2_2") (pintype "input"))
      (node (ref "C12") (pin "2") (pinfunction "2_2") (pintype "input"))
      (node (ref "C13") (pin "2") (pinfunction "2_2") (pintype "input"))
      (node (ref "C3") (pin "2") (pinfunction "2_2") (pintype "input"))
      (node (ref "C4") (pin "2") (pinfunction "2_2") (pintype "input"))
      (node (ref "C9") (pin "2") (pinfunction "2_2") (pintype "input"))
      (node (ref "H1") (pin "4") (pinfunction "4_4") (pintype "unspecified"))
      (node (ref "H2") (pin "3") (pinfunction "3_3") (pintype "unspecified"))
      (node (ref "J1") (pin "17") (pinfunction "17_17") (pintype "unspecified"))
      (node (ref "J1") (pin "3") (pinfunction "3_3") (pintype "unspecified"))
      (node (ref "J2") (pin "1") (pinfunction "1_1") (pintype "unspecified"))
      (node (ref "Q1") (pin "2") (pinfunction "E_2") (pintype "input"))
      (node (ref "R3") (pin "1") (pinfunction "1_1") (pintype "input"))
      (node (ref "R4") (pin "2") (pinfunction "2_2") (pintype "input"))
      (node (ref "R8") (pin "2") (pinfunction "2_2") (pintype "input"))
      (node (ref "R9") (pin "2") (pinfunction "2_2") (pintype "input"))
      (node (ref "SW3") (pin "4") (pinfunction "4_4") (pintype "unspecified"))
      (node (ref "U1") (pin "24") (pinfunction "VDD_1_24") (pintype "unspecified"))
      (node (ref "U1") (pin "36") (pinfunction "VDD_2_36") (pintype "unspecified"))
      (node (ref "U1") (pin "48") (pinfunction "VDD_3_48") (pintype "unspecified"))
      (node (ref "U1") (pin "9") (pinfunction "VDDA_9") (pintype "unspecified"))
      (node (ref "U3") (pin "2") (pinfunction "VOUT(TAB)_2") (pintype "unspecified"))
      (node (ref "U3") (pin "4") (pinfunction "TAB_4") (pintype "unspecified"))
    )
  )
)
